# End_Effector_Board.net
KiCad netlist of a schematic drawn in EAGLE
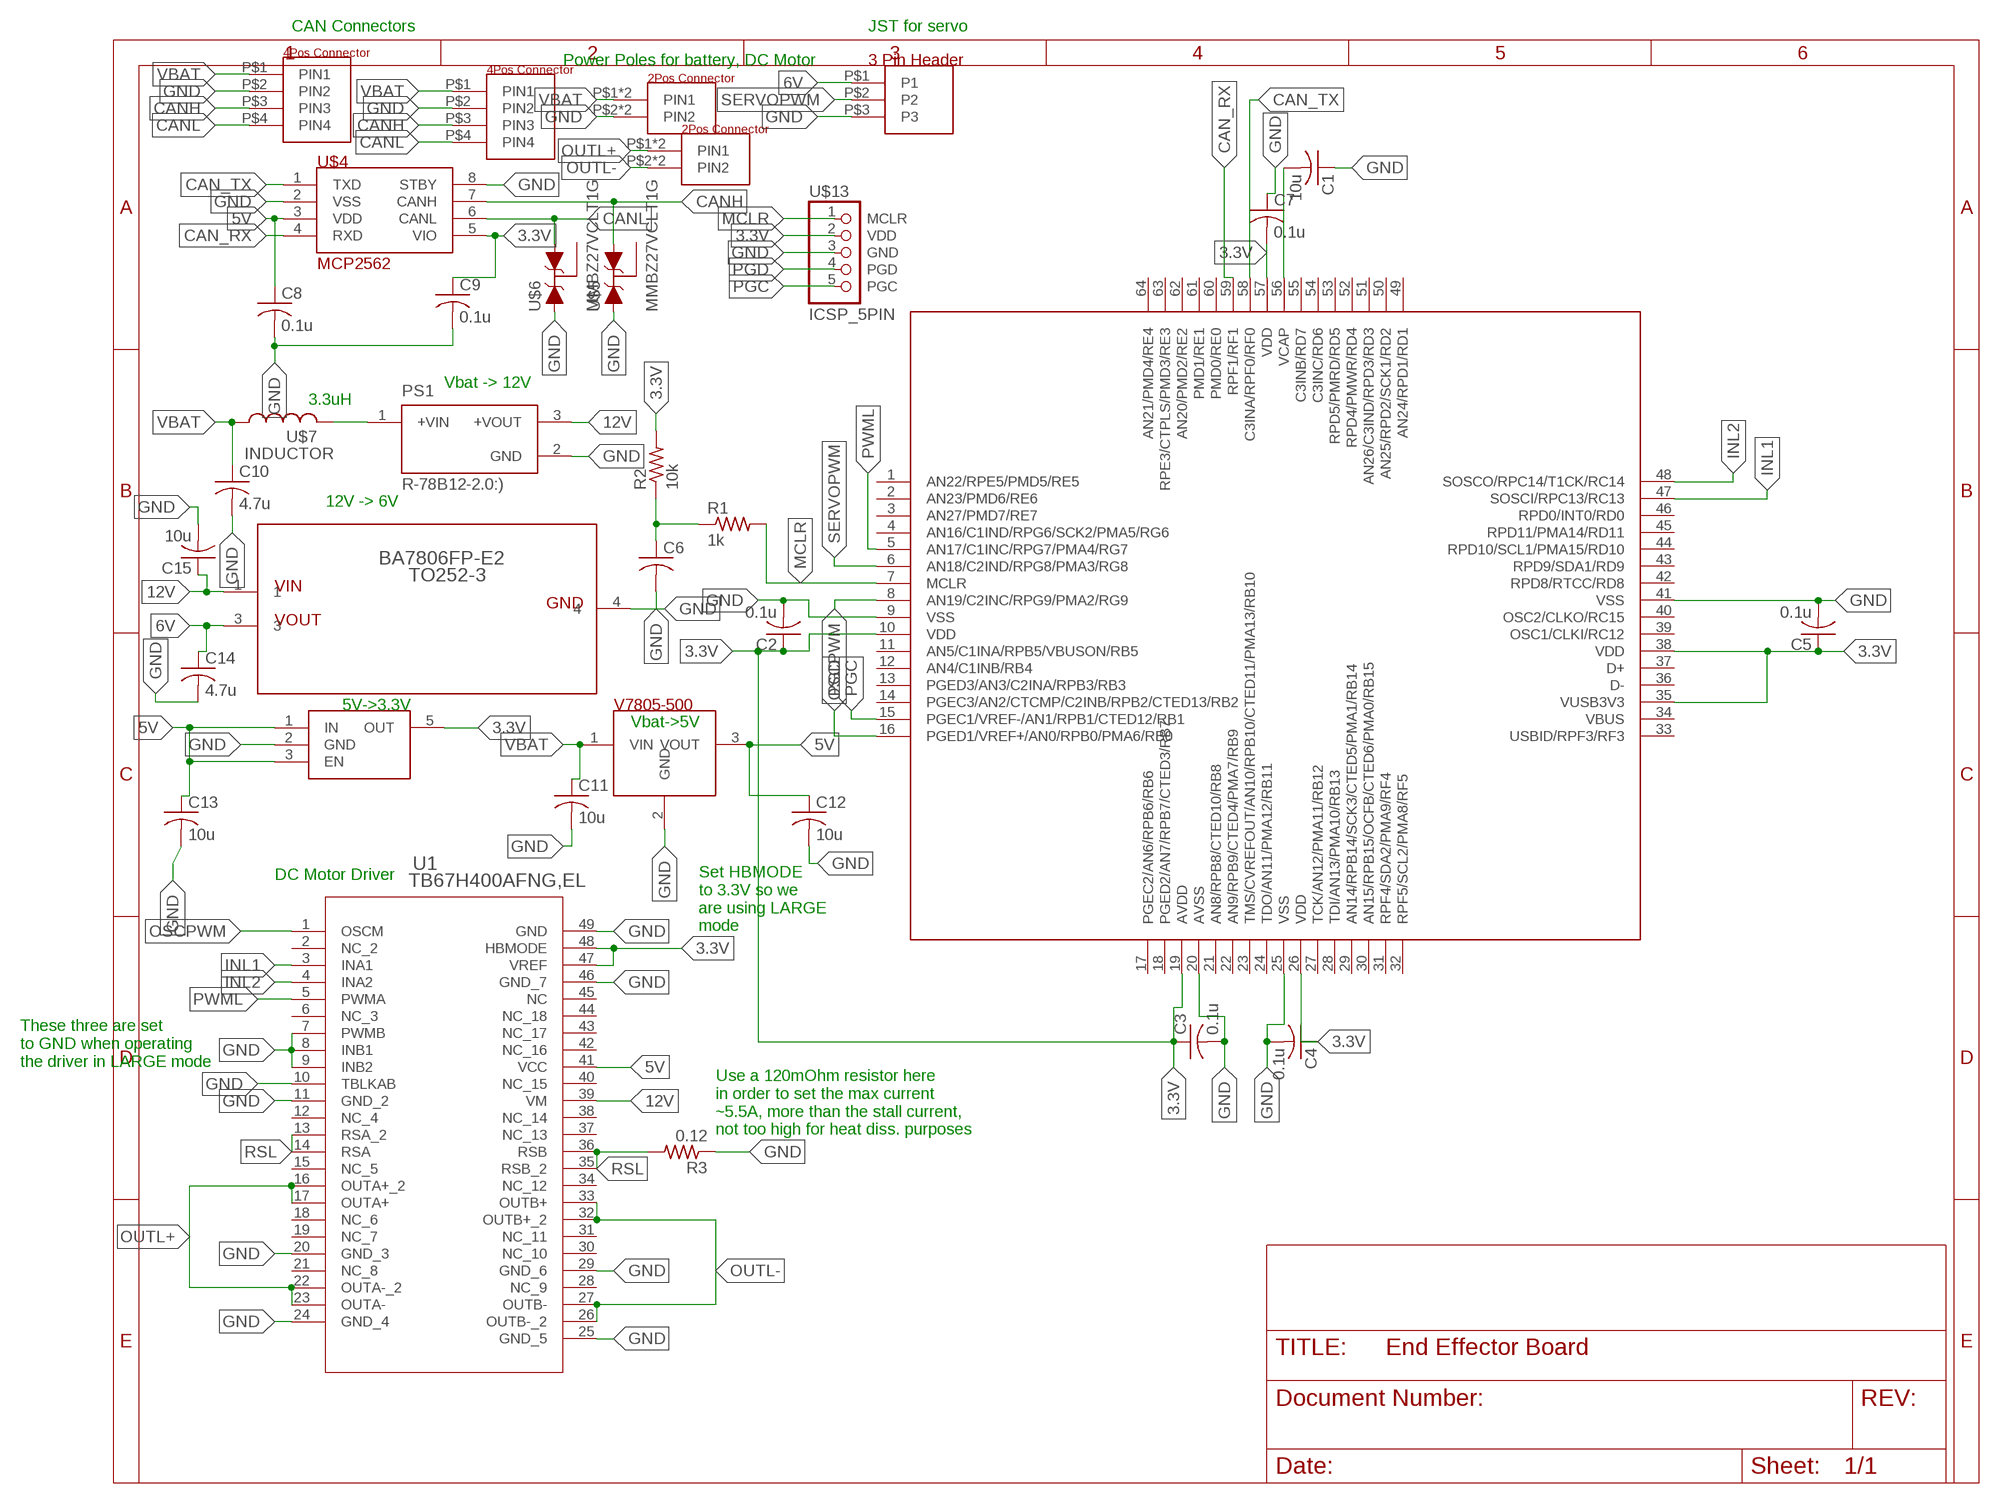
[diagram p0: schematic, sheet 1]

(export (version "E")
  (design (tool "Eeschema 10.0.6"))
  (components
    (comp (ref "BA7806FP-E2")
      (value "TO252-3")
      (footprint "eagle-import:TO252-3")
      (libsource (lib "eagle-import") (part "TO252-3"))
    )
    (comp (ref "C1")
      (value "10u")
      (footprint "eagle-import:C0603")
      (libsource (lib "eagle-import") (part "rcl_334_C-USC0603"))
    )
    (comp (ref "C2")
      (value "0.1u")
      (footprint "eagle-import:C0603")
      (libsource (lib "eagle-import") (part "rcl_334_C-USC0603"))
    )
    (comp (ref "C3")
      (value "0.1u")
      (footprint "eagle-import:C0603")
      (libsource (lib "eagle-import") (part "rcl_334_C-USC0603"))
    )
    (comp (ref "C4")
      (value "0.1u")
      (footprint "eagle-import:C0603")
      (libsource (lib "eagle-import") (part "rcl_334_C-USC0603"))
    )
    (comp (ref "C5")
      (value "0.1u")
      (footprint "eagle-import:C0603")
      (libsource (lib "eagle-import") (part "rcl_334_C-USC0603"))
    )
    (comp (ref "C6")
      (value "C-USC0603")
      (footprint "eagle-import:C0603")
      (libsource (lib "eagle-import") (part "rcl_334_C-USC0603"))
    )
    (comp (ref "C7")
      (value "0.1u")
      (footprint "eagle-import:C0603")
      (libsource (lib "eagle-import") (part "rcl_334_C-USC0603"))
    )
    (comp (ref "C8")
      (value "0.1u")
      (footprint "eagle-import:C0603")
      (libsource (lib "eagle-import") (part "rcl_334_C-USC0603"))
    )
    (comp (ref "C9")
      (value "0.1u")
      (footprint "eagle-import:C0603")
      (libsource (lib "eagle-import") (part "rcl_334_C-USC0603"))
    )
    (comp (ref "C10")
      (value "4.7u")
      (footprint "eagle-import:C0603")
      (libsource (lib "eagle-import") (part "C-USC0603"))
    )
    (comp (ref "C11")
      (value "10u")
      (footprint "eagle-import:C0603")
      (libsource (lib "eagle-import") (part "rcl_334_C-USC0603"))
    )
    (comp (ref "C12")
      (value "10u")
      (footprint "eagle-import:C0603")
      (libsource (lib "eagle-import") (part "rcl_334_C-USC0603"))
    )
    (comp (ref "C13")
      (value "10u")
      (footprint "eagle-import:C0603")
      (libsource (lib "eagle-import") (part "rcl_334_C-USC0603"))
    )
    (comp (ref "C14")
      (value "4.7u")
      (footprint "eagle-import:C0603")
      (libsource (lib "eagle-import") (part "C-USC0603"))
    )
    (comp (ref "C15")
      (value "10u")
      (footprint "eagle-import:C0603")
      (libsource (lib "eagle-import") (part "rcl_334_C-USC0603"))
    )
    (comp (ref "PS1")
      (value "R-78B12-2.0:)")
      (footprint "eagle-import:CONV_R-78B12-2.0")
      (fields
        (field (name "DIGI-KEY_PART_NUMBER") "945-3041-ND")
        (field (name "MF") "Recom Power")
        (field (name "MP") "R-78B12-2.0")
        (field (name "SPICEPREFIX") "J")
      )
      (libsource (lib "eagle-import") (part "R-78B12-2.0{colon})"))
    )
    (comp (ref "R1")
      (value "1k")
      (footprint "eagle-import:R0603")
      (libsource (lib "eagle-import") (part "R-US_R0603"))
    )
    (comp (ref "R2")
      (value "10k")
      (footprint "eagle-import:R0603")
      (libsource (lib "eagle-import") (part "R-US_R0603"))
    )
    (comp (ref "R3")
      (value "0.12")
      (footprint "eagle-import:R0603")
      (libsource (lib "eagle-import") (part "R-US_R0603"))
    )
    (comp (ref "U$1")
      (value "4POS_2ROW_CONNECTOR")
      (footprint "eagle-import:4POS_2ROW_HEADER_.1_")
      (libsource (lib "eagle-import") (part "4POS_2ROW_CONNECTOR"))
    )
    (comp (ref "U$2")
      (value "4POS_2ROW_CONNECTOR")
      (footprint "eagle-import:4POS_2ROW_HEADER_.1_")
      (libsource (lib "eagle-import") (part "4POS_2ROW_CONNECTOR"))
    )
    (comp (ref "U$3")
      (value "PIC32MX530F128HOLD")
      (footprint "eagle-import:TQFP64-10X10X1MM")
      (libsource (lib "eagle-import") (part "PIC32MX530F128HOLD"))
    )
    (comp (ref "U$4")
      (value "MCP2562")
      (footprint "eagle-import:SOIC8")
      (libsource (lib "eagle-import") (part "MCP2562"))
    )
    (comp (ref "U$5")
      (value "MMBZ27VCLT1G")
      (footprint "eagle-import:SOT23")
      (libsource (lib "eagle-import") (part "MMBZ27VCLT1G"))
    )
    (comp (ref "U$6")
      (value "MMBZ27VCLT1G")
      (footprint "eagle-import:SOT23")
      (libsource (lib "eagle-import") (part "MMBZ27VCLT1G"))
    )
    (comp (ref "U$7")
      (value "INDUCTOR")
      (footprint "eagle-import:0603")
      (fields (field (name "SPICEPREFIX") "B"))
      (libsource (lib "eagle-import") (part "INDUCTOR"))
    )
    (comp (ref "U$8")
      (value "TLV70233DBVR")
      (footprint "eagle-import:SOT-23-5")
      (libsource (lib "eagle-import") (part "TLV70233DBVR"))
    )
    (comp (ref "U$9")
      (value "V7805-500")
      (footprint "eagle-import:SIP3")
      (libsource (lib "eagle-import") (part "V7805-500"))
    )
    (comp (ref "U$10")
      (value "2POS_CONNECTOR,1X2_45A_POWERPOLE")
      (footprint "eagle-import:POWERPOLE_45A_1X2")
      (libsource (lib "eagle-import") (part "2POS_CONNECTOR,1X2_45A_POWERPOLE"))
    )
    (comp (ref "U$11")
      (value "2POS_CONNECTOR,1X2_45A_POWERPOLE")
      (footprint "eagle-import:POWERPOLE_45A_1X2")
      (libsource (lib "eagle-import") (part "2POS_CONNECTOR,1X2_45A_POWERPOLE"))
    )
    (comp (ref "U$12")
      (value "3POS_CONNECTORJST-ZH")
      (footprint "eagle-import:3POS_ZH_SIDE")
      (libsource (lib "eagle-import") (part "3POS_CONNECTORJST-ZH"))
    )
    (comp (ref "U$13")
      (value "ICSP_5PIN")
      (footprint "eagle-import:ICSP_5")
      (libsource (lib "eagle-import") (part "ICSP_5PIN"))
    )
    (comp (ref "U1")
      (value "TB67H400AFNG,EL")
      (footprint "eagle-import:HTSSOP48-P-300-0P50_TOS")
      (fields (field (name "COPYRIGHT") "Copyright (C) 2021 Ultra Librarian. All rights reserved."))
      (libsource (lib "eagle-import") (part "TB67H400AFNG,EL"))
    )
  )
  (nets
    (net (code "1") (name "3.3V") (class "Default")
      (node (ref "C2") (pin "1") (pinfunction "1_1") (pintype "passive"))
      (node (ref "C3") (pin "1") (pinfunction "1_1") (pintype "passive"))
      (node (ref "C4") (pin "1") (pinfunction "1_1") (pintype "passive"))
      (node (ref "C5") (pin "1") (pinfunction "1_1") (pintype "passive"))
      (node (ref "C7") (pin "2") (pinfunction "2_2") (pintype "passive"))
      (node (ref "C9") (pin "1") (pinfunction "1_1") (pintype "passive"))
      (node (ref "R2") (pin "2") (pinfunction "2_2") (pintype "passive"))
      (node (ref "U$13") (pin "2") (pinfunction "VDD_2") (pintype "passive"))
      (node (ref "U$3") (pin "10") (pinfunction "VDD_10") (pintype "bidirectional"))
      (node (ref "U$3") (pin "19") (pinfunction "AVDD_19") (pintype "bidirectional"))
      (node (ref "U$3") (pin "26") (pinfunction "VDD_26") (pintype "bidirectional"))
      (node (ref "U$3") (pin "35") (pinfunction "VUSB3V3_35") (pintype "bidirectional"))
      (node (ref "U$3") (pin "38") (pinfunction "VDD_38") (pintype "bidirectional"))
      (node (ref "U$3") (pin "57") (pinfunction "VDD_57") (pintype "bidirectional"))
      (node (ref "U$4") (pin "5") (pinfunction "VIO_5") (pintype "bidirectional"))
      (node (ref "U$8") (pin "5") (pinfunction "OUT_5") (pintype "bidirectional"))
      (node (ref "U1") (pin "47") (pinfunction "VREF_47") (pintype "power_in"))
      (node (ref "U1") (pin "48") (pinfunction "HBMODE_48") (pintype "passive"))
    )
    (net (code "2") (name "5V") (class "Default")
      (node (ref "C12") (pin "1") (pinfunction "1_1") (pintype "passive"))
      (node (ref "C13") (pin "1") (pinfunction "1_1") (pintype "passive"))
      (node (ref "C8") (pin "1") (pinfunction "1_1") (pintype "passive"))
      (node (ref "U$4") (pin "3") (pinfunction "VDD_3") (pintype "power_in"))
      (node (ref "U$8") (pin "1") (pinfunction "IN_1") (pintype "bidirectional"))
      (node (ref "U$8") (pin "3") (pinfunction "EN_3") (pintype "bidirectional"))
      (node (ref "U$9") (pin "3") (pinfunction "VOUT_3") (pintype "bidirectional"))
      (node (ref "U1") (pin "41") (pinfunction "VCC_41") (pintype "power_in"))
    )
    (net (code "3") (name "6V") (class "Default")
      (node (ref "BA7806FP-E2") (pin "3") (pinfunction "3_3") (pintype "passive"))
      (node (ref "C14") (pin "1") (pinfunction "1_1") (pintype "passive"))
      (node (ref "U$12") (pin "P$1") (pinfunction "P1_P$1") (pintype "bidirectional"))
    )
    (net (code "4") (name "12V") (class "Default")
      (node (ref "BA7806FP-E2") (pin "1") (pinfunction "1_1") (pintype "passive"))
      (node (ref "C15") (pin "1") (pinfunction "1_1") (pintype "passive"))
      (node (ref "PS1") (pin "3") (pinfunction "+VOUT_3") (pintype "output"))
      (node (ref "U1") (pin "39") (pinfunction "VM_39") (pintype "passive"))
    )
    (net (code "5") (name "CANH") (class "Default")
      (node (ref "U$1") (pin "P$3") (pinfunction "PIN3_P$3") (pintype "bidirectional"))
      (node (ref "U$2") (pin "P$3") (pinfunction "PIN3_P$3") (pintype "bidirectional"))
      (node (ref "U$4") (pin "7") (pinfunction "CANH_7") (pintype "bidirectional"))
      (node (ref "U$5") (pin "2") (pinfunction "A2_2") (pintype "passive"))
    )
    (net (code "6") (name "CANL") (class "Default")
      (node (ref "U$1") (pin "P$4") (pinfunction "PIN4_P$4") (pintype "bidirectional"))
      (node (ref "U$2") (pin "P$4") (pinfunction "PIN4_P$4") (pintype "bidirectional"))
      (node (ref "U$4") (pin "6") (pinfunction "CANL_6") (pintype "bidirectional"))
      (node (ref "U$6") (pin "2") (pinfunction "A2_2") (pintype "passive"))
    )
    (net (code "7") (name "CAN_RX") (class "Default")
      (node (ref "U$3") (pin "59") (pinfunction "RPF1/RF1_59") (pintype "bidirectional"))
      (node (ref "U$4") (pin "4") (pinfunction "RXD_4") (pintype "input"))
    )
    (net (code "8") (name "CAN_TX") (class "Default")
      (node (ref "U$3") (pin "58") (pinfunction "C3INA/RPF0/RF0_58") (pintype "bidirectional"))
      (node (ref "U$4") (pin "1") (pinfunction "TXD_1") (pintype "output"))
    )
    (net (code "9") (name "GND") (class "Default")
      (node (ref "BA7806FP-E2") (pin "4") (pinfunction "4_4") (pintype "passive"))
      (node (ref "C1") (pin "1") (pinfunction "1_1") (pintype "passive"))
      (node (ref "C10") (pin "2") (pinfunction "2_2") (pintype "passive"))
      (node (ref "C11") (pin "2") (pinfunction "2_2") (pintype "passive"))
      (node (ref "C12") (pin "2") (pinfunction "2_2") (pintype "passive"))
      (node (ref "C13") (pin "2") (pinfunction "2_2") (pintype "passive"))
      (node (ref "C14") (pin "2") (pinfunction "2_2") (pintype "passive"))
      (node (ref "C15") (pin "2") (pinfunction "2_2") (pintype "passive"))
      (node (ref "C2") (pin "2") (pinfunction "2_2") (pintype "passive"))
      (node (ref "C3") (pin "2") (pinfunction "2_2") (pintype "passive"))
      (node (ref "C4") (pin "2") (pinfunction "2_2") (pintype "passive"))
      (node (ref "C5") (pin "2") (pinfunction "2_2") (pintype "passive"))
      (node (ref "C6") (pin "2") (pinfunction "2_2") (pintype "passive"))
      (node (ref "C7") (pin "1") (pinfunction "1_1") (pintype "passive"))
      (node (ref "C8") (pin "2") (pinfunction "2_2") (pintype "passive"))
      (node (ref "C9") (pin "2") (pinfunction "2_2") (pintype "passive"))
      (node (ref "PS1") (pin "2") (pinfunction "GND_2") (pintype "power_in"))
      (node (ref "R3") (pin "1") (pinfunction "1_1") (pintype "passive"))
      (node (ref "U$1") (pin "P$2") (pinfunction "PIN2_P$2") (pintype "bidirectional"))
      (node (ref "U$10") (pin "P$2") (pinfunction "PIN2_P$2") (pintype "bidirectional"))
      (node (ref "U$10") (pin "P$6") (pinfunction "PIN2_P$6") (pintype "bidirectional"))
      (node (ref "U$12") (pin "P$3") (pinfunction "P3_P$3") (pintype "bidirectional"))
      (node (ref "U$13") (pin "3") (pinfunction "GND_3") (pintype "passive"))
      (node (ref "U$2") (pin "P$2") (pinfunction "PIN2_P$2") (pintype "bidirectional"))
      (node (ref "U$3") (pin "20") (pinfunction "AVSS_20") (pintype "bidirectional"))
      (node (ref "U$3") (pin "25") (pinfunction "VSS_25") (pintype "bidirectional"))
      (node (ref "U$3") (pin "41") (pinfunction "VSS_41") (pintype "bidirectional"))
      (node (ref "U$3") (pin "9") (pinfunction "VSS_9") (pintype "bidirectional"))
      (node (ref "U$4") (pin "2") (pinfunction "VSS_2") (pintype "power_in"))
      (node (ref "U$4") (pin "8") (pinfunction "STBY_8") (pintype "input"))
      (node (ref "U$5") (pin "1") (pinfunction "A1_1") (pintype "passive"))
      (node (ref "U$6") (pin "1") (pinfunction "A1_1") (pintype "passive"))
      (node (ref "U$8") (pin "2") (pinfunction "GND_2") (pintype "bidirectional"))
      (node (ref "U$9") (pin "2") (pinfunction "GND_2") (pintype "bidirectional"))
      (node (ref "U1") (pin "10") (pinfunction "TBLKAB_10") (pintype "passive"))
      (node (ref "U1") (pin "11") (pinfunction "GND_2_11") (pintype "passive"))
      (node (ref "U1") (pin "20") (pinfunction "GND_3_20") (pintype "passive"))
      (node (ref "U1") (pin "24") (pinfunction "GND_4_24") (pintype "passive"))
      (node (ref "U1") (pin "25") (pinfunction "GND_5_25") (pintype "passive"))
      (node (ref "U1") (pin "29") (pinfunction "GND_6_29") (pintype "passive"))
      (node (ref "U1") (pin "46") (pinfunction "GND_7_46") (pintype "passive"))
      (node (ref "U1") (pin "49") (pinfunction "GND_49") (pintype "passive"))
      (node (ref "U1") (pin "7") (pinfunction "PWMB_7") (pintype "passive"))
      (node (ref "U1") (pin "8") (pinfunction "INB1_8") (pintype "input"))
      (node (ref "U1") (pin "9") (pinfunction "INB2_9") (pintype "input"))
    )
    (net (code "10") (name "INL1") (class "Default")
      (node (ref "U$3") (pin "47") (pinfunction "SOSCI/RPC13/RC13_47") (pintype "bidirectional"))
      (node (ref "U1") (pin "3") (pinfunction "INA1_3") (pintype "input"))
    )
    (net (code "11") (name "INL2") (class "Default")
      (node (ref "U$3") (pin "48") (pinfunction "SOSCO/RPC14/T1CK/RC14_48") (pintype "bidirectional"))
      (node (ref "U1") (pin "4") (pinfunction "INA2_4") (pintype "input"))
    )
    (net (code "12") (name "MCLR") (class "Default")
      (node (ref "R1") (pin "2") (pinfunction "2_2") (pintype "passive"))
      (node (ref "U$13") (pin "1") (pinfunction "MCLR_1") (pintype "passive"))
      (node (ref "U$3") (pin "7") (pinfunction "MCLR_7") (pintype "bidirectional"))
    )
    (net (code "13") (name "Net-(C6-Pad1)") (class "Default")
      (node (ref "C6") (pin "1") (pinfunction "1_1") (pintype "passive"))
      (node (ref "R1") (pin "1") (pinfunction "1_1") (pintype "passive"))
      (node (ref "R2") (pin "1") (pinfunction "1_1") (pintype "passive"))
    )
    (net (code "14") (name "Net-(PS1-+VIN)") (class "Default")
      (node (ref "PS1") (pin "1") (pinfunction "+VIN_1") (pintype "input"))
      (node (ref "U$7") (pin "2") (pinfunction "2_2") (pintype "passive"))
    )
    (net (code "15") (name "Net-(U$3-VCAP)") (class "Default")
      (node (ref "C1") (pin "2") (pinfunction "2_2") (pintype "passive"))
      (node (ref "U$3") (pin "56") (pinfunction "VCAP_56") (pintype "bidirectional"))
    )
    (net (code "16") (name "OSCPWM") (class "Default")
      (node (ref "U$3") (pin "8") (pinfunction "AN19/C2INC/RPG9/PMA2/RG9_8") (pintype "bidirectional"))
      (node (ref "U1") (pin "1") (pinfunction "OSCM_1") (pintype "passive"))
    )
    (net (code "17") (name "OUTL+") (class "Default")
      (node (ref "U$11") (pin "P$1") (pinfunction "PIN1_P$1") (pintype "bidirectional"))
      (node (ref "U$11") (pin "P$5") (pinfunction "PIN1_P$5") (pintype "bidirectional"))
      (node (ref "U1") (pin "16") (pinfunction "OUTA+_2_16") (pintype "output"))
      (node (ref "U1") (pin "17") (pinfunction "OUTA+_17") (pintype "output"))
      (node (ref "U1") (pin "22") (pinfunction "OUTA-_2_22") (pintype "output"))
      (node (ref "U1") (pin "23") (pinfunction "OUTA-_23") (pintype "output"))
    )
    (net (code "18") (name "OUTL-") (class "Default")
      (node (ref "U$11") (pin "P$2") (pinfunction "PIN2_P$2") (pintype "bidirectional"))
      (node (ref "U$11") (pin "P$6") (pinfunction "PIN2_P$6") (pintype "bidirectional"))
      (node (ref "U1") (pin "26") (pinfunction "OUTB-_2_26") (pintype "output"))
      (node (ref "U1") (pin "27") (pinfunction "OUTB-_27") (pintype "output"))
      (node (ref "U1") (pin "32") (pinfunction "OUTB+_2_32") (pintype "output"))
      (node (ref "U1") (pin "33") (pinfunction "OUTB+_33") (pintype "output"))
    )
    (net (code "19") (name "PGC") (class "Default")
      (node (ref "U$13") (pin "5") (pinfunction "PGC_5") (pintype "passive"))
      (node (ref "U$3") (pin "15") (pinfunction "PGEC1/VREF-/AN1/RPB1/CTED12/RB1_15") (pintype "bidirectional"))
    )
    (net (code "20") (name "PGD") (class "Default")
      (node (ref "U$13") (pin "4") (pinfunction "PGD_4") (pintype "passive"))
      (node (ref "U$3") (pin "16") (pinfunction "PGED1/VREF+/AN0/RPB0/PMA6/RB0_16") (pintype "bidirectional"))
    )
    (net (code "21") (name "PWML") (class "Default")
      (node (ref "U$3") (pin "5") (pinfunction "AN17/C1INC/RPG7/PMA4/RG7_5") (pintype "bidirectional"))
      (node (ref "U1") (pin "5") (pinfunction "PWMA_5") (pintype "passive"))
    )
    (net (code "22") (name "RSL") (class "Default")
      (node (ref "R3") (pin "2") (pinfunction "2_2") (pintype "passive"))
      (node (ref "U1") (pin "13") (pinfunction "RSA_2_13") (pintype "passive"))
      (node (ref "U1") (pin "14") (pinfunction "RSA_14") (pintype "passive"))
      (node (ref "U1") (pin "35") (pinfunction "RSB_2_35") (pintype "passive"))
      (node (ref "U1") (pin "36") (pinfunction "RSB_36") (pintype "passive"))
    )
    (net (code "23") (name "SERVOPWM") (class "Default")
      (node (ref "U$12") (pin "P$2") (pinfunction "P2_P$2") (pintype "bidirectional"))
      (node (ref "U$3") (pin "6") (pinfunction "AN18/C2IND/RPG8/PMA3/RG8_6") (pintype "bidirectional"))
    )
    (net (code "24") (name "VBAT") (class "Default")
      (node (ref "C10") (pin "1") (pinfunction "1_1") (pintype "passive"))
      (node (ref "C11") (pin "1") (pinfunction "1_1") (pintype "passive"))
      (node (ref "U$1") (pin "P$1") (pinfunction "PIN1_P$1") (pintype "bidirectional"))
      (node (ref "U$10") (pin "P$1") (pinfunction "PIN1_P$1") (pintype "bidirectional"))
      (node (ref "U$10") (pin "P$5") (pinfunction "PIN1_P$5") (pintype "bidirectional"))
      (node (ref "U$2") (pin "P$1") (pinfunction "PIN1_P$1") (pintype "bidirectional"))
      (node (ref "U$7") (pin "1") (pinfunction "1_1") (pintype "passive"))
      (node (ref "U$9") (pin "1") (pinfunction "VIN_1") (pintype "bidirectional"))
    )
    (net (code "25") (name "unconnected-(U$3-AN4{slash}C1INB{slash}RB4-Pad12)") (class "Default")
      (node (ref "U$3") (pin "12") (pinfunction "AN4/C1INB/RB4_12") (pintype "bidirectional"))
    )
    (net (code "26") (name "unconnected-(U$3-AN5{slash}C1INA{slash}RPB5{slash}VBUSON{slash}RB5-Pad11)") (class "Default")
      (node (ref "U$3") (pin "11") (pinfunction "AN5/C1INA/RPB5/VBUSON/RB5_11") (pintype "bidirectional"))
    )
    (net (code "27") (name "unconnected-(U$3-AN8{slash}RPB8{slash}CTED10{slash}RB8-Pad21)") (class "Default")
      (node (ref "U$3") (pin "21") (pinfunction "AN8/RPB8/CTED10/RB8_21") (pintype "bidirectional"))
    )
    (net (code "28") (name "unconnected-(U$3-AN9{slash}RPB9{slash}CTED4{slash}PMA7{slash}RB9-Pad22)") (class "Default")
      (node (ref "U$3") (pin "22") (pinfunction "AN9/RPB9/CTED4/PMA7/RB9_22") (pintype "bidirectional"))
    )
    (net (code "29") (name "unconnected-(U$3-AN14{slash}RPB14{slash}SCK3{slash}CTED5{slash}PMA1{slash}RB14-Pad29)") (class "Default")
      (node (ref "U$3") (pin "29") (pinfunction "AN14/RPB14/SCK3/CTED5/PMA1/RB14_29") (pintype "bidirectional"))
    )
    (net (code "30") (name "unconnected-(U$3-AN15{slash}RPB15{slash}OCFB{slash}CTED6{slash}PMA0{slash}RB15-Pad30)") (class "Default")
      (node (ref "U$3") (pin "30") (pinfunction "AN15/RPB15/OCFB/CTED6/PMA0/RB15_30") (pintype "bidirectional"))
    )
    (net (code "31") (name "unconnected-(U$3-AN16{slash}C1IND{slash}RPG6{slash}SCK2{slash}PMA5{slash}RG6-Pad4)") (class "Default")
      (node (ref "U$3") (pin "4") (pinfunction "AN16/C1IND/RPG6/SCK2/PMA5/RG6_4") (pintype "bidirectional"))
    )
    (net (code "32") (name "unconnected-(U$3-AN20{slash}PMD2{slash}RE2-Pad62)") (class "Default")
      (node (ref "U$3") (pin "62") (pinfunction "AN20/PMD2/RE2_62") (pintype "bidirectional"))
    )
    (net (code "33") (name "unconnected-(U$3-AN21{slash}PMD4{slash}RE4-Pad64)") (class "Default")
      (node (ref "U$3") (pin "64") (pinfunction "AN21/PMD4/RE4_64") (pintype "bidirectional"))
    )
    (net (code "34") (name "unconnected-(U$3-AN22{slash}RPE5{slash}PMD5{slash}RE5-Pad1)") (class "Default")
      (node (ref "U$3") (pin "1") (pinfunction "AN22/RPE5/PMD5/RE5_1") (pintype "bidirectional"))
    )
    (net (code "35") (name "unconnected-(U$3-AN23{slash}PMD6{slash}RE6-Pad2)") (class "Default")
      (node (ref "U$3") (pin "2") (pinfunction "AN23/PMD6/RE6_2") (pintype "bidirectional"))
    )
    (net (code "36") (name "unconnected-(U$3-AN24{slash}RPD1{slash}RD1-Pad49)") (class "Default")
      (node (ref "U$3") (pin "49") (pinfunction "AN24/RPD1/RD1_49") (pintype "bidirectional"))
    )
    (net (code "37") (name "unconnected-(U$3-AN25{slash}RPD2{slash}SCK1{slash}RD2-Pad50)") (class "Default")
      (node (ref "U$3") (pin "50") (pinfunction "AN25/RPD2/SCK1/RD2_50") (pintype "bidirectional"))
    )
    (net (code "38") (name "unconnected-(U$3-AN26{slash}C3IND{slash}RPD3{slash}RD3-Pad51)") (class "Default")
      (node (ref "U$3") (pin "51") (pinfunction "AN26/C3IND/RPD3/RD3_51") (pintype "bidirectional"))
    )
    (net (code "39") (name "unconnected-(U$3-AN27{slash}PMD7{slash}RE7-Pad3)") (class "Default")
      (node (ref "U$3") (pin "3") (pinfunction "AN27/PMD7/RE7_3") (pintype "bidirectional"))
    )
    (net (code "40") (name "unconnected-(U$3-C3INB{slash}RD7-Pad55)") (class "Default")
      (node (ref "U$3") (pin "55") (pinfunction "C3INB/RD7_55") (pintype "bidirectional"))
    )
    (net (code "41") (name "unconnected-(U$3-C3INC{slash}RD6-Pad54)") (class "Default")
      (node (ref "U$3") (pin "54") (pinfunction "C3INC/RD6_54") (pintype "bidirectional"))
    )
    (net (code "42") (name "unconnected-(U$3-D+-Pad37)") (class "Default")
      (node (ref "U$3") (pin "37") (pinfunction "D+_37") (pintype "bidirectional"))
    )
    (net (code "43") (name "unconnected-(U$3-D--Pad36)") (class "Default")
      (node (ref "U$3") (pin "36") (pinfunction "D-_36") (pintype "bidirectional"))
    )
    (net (code "44") (name "unconnected-(U$3-OSC1{slash}CLKI{slash}RC12-Pad39)") (class "Default")
      (node (ref "U$3") (pin "39") (pinfunction "OSC1/CLKI/RC12_39") (pintype "bidirectional"))
    )
    (net (code "45") (name "unconnected-(U$3-OSC2{slash}CLKO{slash}RC15-Pad40)") (class "Default")
      (node (ref "U$3") (pin "40") (pinfunction "OSC2/CLKO/RC15_40") (pintype "bidirectional"))
    )
    (net (code "46") (name "unconnected-(U$3-PGEC2{slash}AN6{slash}RPB6{slash}RB6-Pad17)") (class "Default")
      (node (ref "U$3") (pin "17") (pinfunction "PGEC2/AN6/RPB6/RB6_17") (pintype "bidirectional"))
    )
    (net (code "47") (name "unconnected-(U$3-PGEC3{slash}AN2{slash}CTCMP{slash}C2INB{slash}RPB2{slash}CTED13{slash}RB2-Pad14)") (class "Default")
      (node (ref "U$3") (pin "14") (pinfunction "PGEC3/AN2/CTCMP/C2INB/RPB2/CTED13/RB2_14") (pintype "bidirectional"))
    )
    (net (code "48") (name "unconnected-(U$3-PGED2{slash}AN7{slash}RPB7{slash}CTED3{slash}RB7-Pad18)") (class "Default")
      (node (ref "U$3") (pin "18") (pinfunction "PGED2/AN7/RPB7/CTED3/RB7_18") (pintype "bidirectional"))
    )
    (net (code "49") (name "unconnected-(U$3-PGED3{slash}AN3{slash}C2INA{slash}RPB3{slash}RB3-Pad13)") (class "Default")
      (node (ref "U$3") (pin "13") (pinfunction "PGED3/AN3/C2INA/RPB3/RB3_13") (pintype "bidirectional"))
    )
    (net (code "50") (name "unconnected-(U$3-PMD0{slash}RE0-Pad60)") (class "Default")
      (node (ref "U$3") (pin "60") (pinfunction "PMD0/RE0_60") (pintype "bidirectional"))
    )
    (net (code "51") (name "unconnected-(U$3-PMD1{slash}RE1-Pad61)") (class "Default")
      (node (ref "U$3") (pin "61") (pinfunction "PMD1/RE1_61") (pintype "bidirectional"))
    )
    (net (code "52") (name "unconnected-(U$3-RPD0{slash}INT0{slash}RD0-Pad46)") (class "Default")
      (node (ref "U$3") (pin "46") (pinfunction "RPD0/INT0/RD0_46") (pintype "bidirectional"))
    )
    (net (code "53") (name "unconnected-(U$3-RPD4{slash}PMWR{slash}RD4-Pad52)") (class "Default")
      (node (ref "U$3") (pin "52") (pinfunction "RPD4/PMWR/RD4_52") (pintype "bidirectional"))
    )
    (net (code "54") (name "unconnected-(U$3-RPD5{slash}PMRD{slash}RD5-Pad53)") (class "Default")
      (node (ref "U$3") (pin "53") (pinfunction "RPD5/PMRD/RD5_53") (pintype "bidirectional"))
    )
    (net (code "55") (name "unconnected-(U$3-RPD8{slash}RTCC{slash}RD8-Pad42)") (class "Default")
      (node (ref "U$3") (pin "42") (pinfunction "RPD8/RTCC/RD8_42") (pintype "bidirectional"))
    )
    (net (code "56") (name "unconnected-(U$3-RPD9{slash}SDA1{slash}RD9-Pad43)") (class "Default")
      (node (ref "U$3") (pin "43") (pinfunction "RPD9/SDA1/RD9_43") (pintype "bidirectional"))
    )
    (net (code "57") (name "unconnected-(U$3-RPD10{slash}SCL1{slash}PMA15{slash}RD10-Pad44)") (class "Default")
      (node (ref "U$3") (pin "44") (pinfunction "RPD10/SCL1/PMA15/RD10_44") (pintype "bidirectional"))
    )
    (net (code "58") (name "unconnected-(U$3-RPD11{slash}PMA14{slash}RD11-Pad45)") (class "Default")
      (node (ref "U$3") (pin "45") (pinfunction "RPD11/PMA14/RD11_45") (pintype "bidirectional"))
    )
    (net (code "59") (name "unconnected-(U$3-RPE3{slash}CTPLS{slash}PMD3{slash}RE3-Pad63)") (class "Default")
      (node (ref "U$3") (pin "63") (pinfunction "RPE3/CTPLS/PMD3/RE3_63") (pintype "bidirectional"))
    )
    (net (code "60") (name "unconnected-(U$3-RPF4{slash}SDA2{slash}PMA9{slash}RF4-Pad31)") (class "Default")
      (node (ref "U$3") (pin "31") (pinfunction "RPF4/SDA2/PMA9/RF4_31") (pintype "bidirectional"))
    )
    (net (code "61") (name "unconnected-(U$3-RPF5{slash}SCL2{slash}PMA8{slash}RF5-Pad32)") (class "Default")
      (node (ref "U$3") (pin "32") (pinfunction "RPF5/SCL2/PMA8/RF5_32") (pintype "bidirectional"))
    )
    (net (code "62") (name "unconnected-(U$3-TCK{slash}AN12{slash}PMA11{slash}RB12-Pad27)") (class "Default")
      (node (ref "U$3") (pin "27") (pinfunction "TCK/AN12/PMA11/RB12_27") (pintype "bidirectional"))
    )
    (net (code "63") (name "unconnected-(U$3-TDI{slash}AN13{slash}PMA10{slash}RB13-Pad28)") (class "Default")
      (node (ref "U$3") (pin "28") (pinfunction "TDI/AN13/PMA10/RB13_28") (pintype "bidirectional"))
    )
    (net (code "64") (name "unconnected-(U$3-TDO{slash}AN11{slash}PMA12{slash}RB11-Pad24)") (class "Default")
      (node (ref "U$3") (pin "24") (pinfunction "TDO/AN11/PMA12/RB11_24") (pintype "bidirectional"))
    )
    (net (code "65") (name "unconnected-(U$3-TMS{slash}CVREFOUT{slash}AN10{slash}RPB10{slash}CTED11{slash}PMA13{slash}RB10-Pad23)") (class "Default")
      (node (ref "U$3") (pin "23") (pinfunction "TMS/CVREFOUT/AN10/RPB10/CTED11/PMA13/RB10_23") (pintype "bidirectional"))
    )
    (net (code "66") (name "unconnected-(U$3-USBID{slash}RPF3{slash}RF3-Pad33)") (class "Default")
      (node (ref "U$3") (pin "33") (pinfunction "USBID/RPF3/RF3_33") (pintype "bidirectional"))
    )
    (net (code "67") (name "unconnected-(U$3-VBUS-Pad34)") (class "Default")
      (node (ref "U$3") (pin "34") (pinfunction "VBUS_34") (pintype "bidirectional"))
    )
    (net (code "68") (name "unconnected-(U$5-C-Pad3)") (class "Default")
      (node (ref "U$5") (pin "3") (pinfunction "C_3") (pintype "bidirectional"))
    )
    (net (code "69") (name "unconnected-(U$6-C-Pad3)") (class "Default")
      (node (ref "U$6") (pin "3") (pinfunction "C_3") (pintype "bidirectional"))
    )
    (net (code "70") (name "unconnected-(U1-NC-Pad45)") (class "Default")
      (node (ref "U1") (pin "45") (pinfunction "NC_45") (pintype "no_connect"))
    )
    (net (code "71") (name "unconnected-(U1-NC_2-Pad2)") (class "Default")
      (node (ref "U1") (pin "2") (pinfunction "NC_2_2") (pintype "no_connect"))
    )
    (net (code "72") (name "unconnected-(U1-NC_3-Pad6)") (class "Default")
      (node (ref "U1") (pin "6") (pinfunction "NC_3_6") (pintype "no_connect"))
    )
    (net (code "73") (name "unconnected-(U1-NC_4-Pad12)") (class "Default")
      (node (ref "U1") (pin "12") (pinfunction "NC_4_12") (pintype "no_connect"))
    )
    (net (code "74") (name "unconnected-(U1-NC_5-Pad15)") (class "Default")
      (node (ref "U1") (pin "15") (pinfunction "NC_5_15") (pintype "no_connect"))
    )
    (net (code "75") (name "unconnected-(U1-NC_6-Pad18)") (class "Default")
      (node (ref "U1") (pin "18") (pinfunction "NC_6_18") (pintype "no_connect"))
    )
    (net (code "76") (name "unconnected-(U1-NC_7-Pad19)") (class "Default")
      (node (ref "U1") (pin "19") (pinfunction "NC_7_19") (pintype "no_connect"))
    )
    (net (code "77") (name "unconnected-(U1-NC_8-Pad21)") (class "Default")
      (node (ref "U1") (pin "21") (pinfunction "NC_8_21") (pintype "no_connect"))
    )
    (net (code "78") (name "unconnected-(U1-NC_9-Pad28)") (class "Default")
      (node (ref "U1") (pin "28") (pinfunction "NC_9_28") (pintype "no_connect"))
    )
    (net (code "79") (name "unconnected-(U1-NC_10-Pad30)") (class "Default")
      (node (ref "U1") (pin "30") (pinfunction "NC_10_30") (pintype "no_connect"))
    )
    (net (code "80") (name "unconnected-(U1-NC_11-Pad31)") (class "Default")
      (node (ref "U1") (pin "31") (pinfunction "NC_11_31") (pintype "no_connect"))
    )
    (net (code "81") (name "unconnected-(U1-NC_12-Pad34)") (class "Default")
      (node (ref "U1") (pin "34") (pinfunction "NC_12_34") (pintype "no_connect"))
    )
    (net (code "82") (name "unconnected-(U1-NC_13-Pad37)") (class "Default")
      (node (ref "U1") (pin "37") (pinfunction "NC_13_37") (pintype "no_connect"))
    )
    (net (code "83") (name "unconnected-(U1-NC_14-Pad38)") (class "Default")
      (node (ref "U1") (pin "38") (pinfunction "NC_14_38") (pintype "no_connect"))
    )
    (net (code "84") (name "unconnected-(U1-NC_15-Pad40)") (class "Default")
      (node (ref "U1") (pin "40") (pinfunction "NC_15_40") (pintype "no_connect"))
    )
    (net (code "85") (name "unconnected-(U1-NC_16-Pad42)") (class "Default")
      (node (ref "U1") (pin "42") (pinfunction "NC_16_42") (pintype "no_connect"))
    )
    (net (code "86") (name "unconnected-(U1-NC_17-Pad43)") (class "Default")
      (node (ref "U1") (pin "43") (pinfunction "NC_17_43") (pintype "no_connect"))
    )
    (net (code "87") (name "unconnected-(U1-NC_18-Pad44)") (class "Default")
      (node (ref "U1") (pin "44") (pinfunction "NC_18_44") (pintype "no_connect"))
    )
  )
)
